# Dust1_carrier_6.net
KiCad netlist of a schematic drawn in Altium Designer
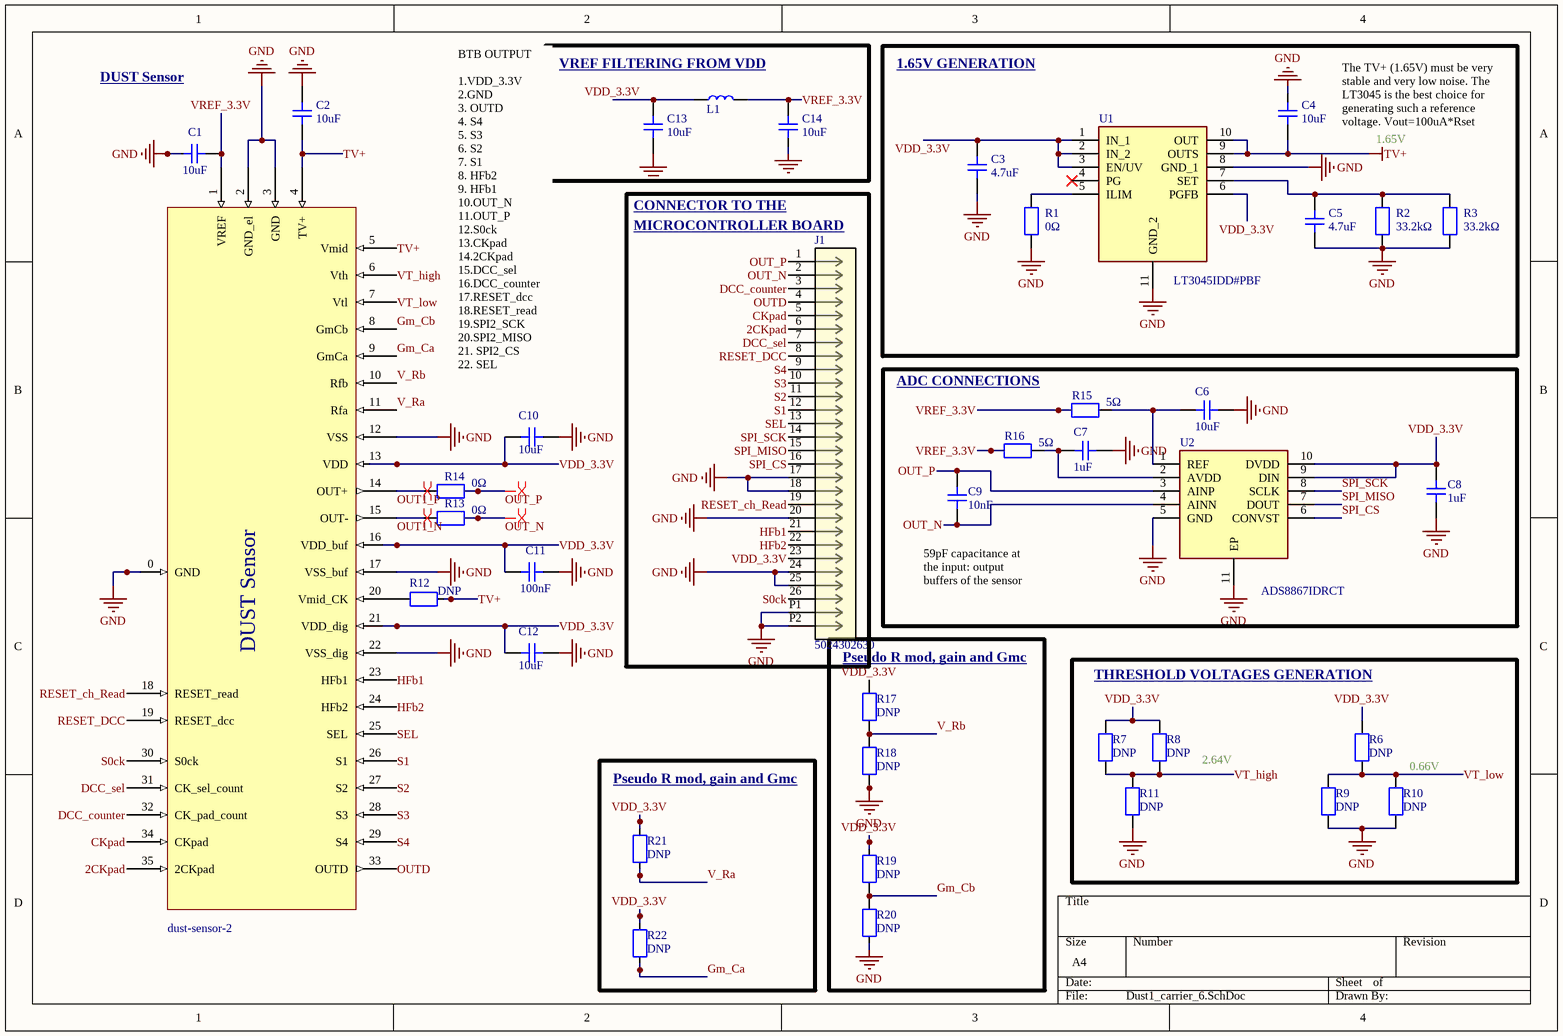
[diagram p0: Dust1_carrier_6.SchDoc]

(export (version "E")
  (design (tool "Eeschema 10.0.6"))
  (components
    (comp (ref "C1")
      (value "10uF")
      (footprint "CAP_0402")
      (libsource (lib "I3N - LABSAMP") (part "CAP_0402"))
    )
    (comp (ref "C2")
      (value "10uF")
      (footprint "CAP_0402")
      (libsource (lib "I3N - LABSAMP") (part "CAP_0402"))
    )
    (comp (ref "C3")
      (value "4.7uF")
      (footprint "CAP_0402")
      (libsource (lib "I3N - LABSAMP") (part "CAP_0402"))
    )
    (comp (ref "C4")
      (value "10uF")
      (footprint "CAP_0402")
      (libsource (lib "I3N - LABSAMP") (part "CAP_0402"))
    )
    (comp (ref "C5")
      (value "4.7uF")
      (footprint "CAP_0402")
      (libsource (lib "I3N - LABSAMP") (part "CAP_0402"))
    )
    (comp (ref "C6")
      (value "10uF")
      (footprint "CAP_0402")
      (libsource (lib "I3N - LABSAMP") (part "CAP_0402"))
    )
    (comp (ref "C7") (value "1uF") (footprint "CAP_0402") (libsource (lib "I3N - LABSAMP") (part "CAP_0402")))
    (comp (ref "C8") (value "1uF") (footprint "CAP_0402") (libsource (lib "I3N - LABSAMP") (part "CAP_0402")))
    (comp (ref "C9")
      (value "10nF")
      (footprint "CAP_0402")
      (libsource (lib "I3N - LABSAMP") (part "CAP_0402"))
    )
    (comp (ref "C10")
      (value "10uF")
      (footprint "CAP_0402")
      (libsource (lib "I3N - LABSAMP") (part "CAP_0402"))
    )
    (comp (ref "C11")
      (value "100nF")
      (footprint "CAP_0402")
      (libsource (lib "I3N - LABSAMP") (part "CAP_0402"))
    )
    (comp (ref "C12")
      (value "10uF")
      (footprint "CAP_0402")
      (libsource (lib "I3N - LABSAMP") (part "CAP_0402"))
    )
    (comp (ref "C13")
      (value "10uF")
      (footprint "CAP_0402")
      (libsource (lib "I3N - LABSAMP") (part "CAP_0402"))
    )
    (comp (ref "C14")
      (value "10uF")
      (footprint "CAP_0402")
      (libsource (lib "I3N - LABSAMP") (part "CAP_0402"))
    )
    (comp (ref "dust-sensor-2")
      (value "dust-sensor-2")
      (footprint "dust-sensor-2-Footprint-1")
      (description "dust-sensor-v2-2025")
      (libsource (lib "I3N - LABSAMP") (part "GND"))
    )
    (comp (ref "J1")
      (value "5024302630")
      (footprint "CON_5024302630_MOL")
      (fields (field (name "COPYRIGHT") "Copyright (C) 2025 Ultra Librarian. All rights reserved."))
      (libsource (lib "I3N - LABSAMP") (part "5024302630"))
    )
    (comp (ref "L1")
      (value "IND_0603")
      (footprint "IND_0603")
      (description "Generic 0603 Inductor")
      (libsource (lib "I3N - LABSAMP") (part "IND_0603"))
    )
    (comp (ref "R1")
      (value "0Ω")
      (footprint "RES_0402")
      (description "Resistor SMD 0402 Generic")
      (libsource (lib "I3N - LABSAMP") (part "RES_0402"))
    )
    (comp (ref "R2")
      (value "33.2kΩ")
      (footprint "RES_0402")
      (description "Resistor SMD 0402 Generic")
      (libsource (lib "I3N - LABSAMP") (part "RES_0402"))
    )
    (comp (ref "R3")
      (value "33.2kΩ")
      (footprint "RES_0402")
      (description "Resistor SMD 0402 Generic")
      (libsource (lib "I3N - LABSAMP") (part "RES_0402"))
    )
    (comp (ref "R6")
      (value "DNP")
      (footprint "RES_0402")
      (description "Resistor SMD 0402 Generic")
      (libsource (lib "I3N - LABSAMP") (part "RES_0402"))
    )
    (comp (ref "R7")
      (value "DNP")
      (footprint "RES_0402")
      (description "Resistor SMD 0402 Generic")
      (libsource (lib "I3N - LABSAMP") (part "RES_0402"))
    )
    (comp (ref "R8")
      (value "DNP")
      (footprint "RES_0402")
      (description "Resistor SMD 0402 Generic")
      (libsource (lib "I3N - LABSAMP") (part "RES_0402"))
    )
    (comp (ref "R9")
      (value "DNP")
      (footprint "RES_0402")
      (description "Resistor SMD 0402 Generic")
      (libsource (lib "I3N - LABSAMP") (part "RES_0402"))
    )
    (comp (ref "R10")
      (value "DNP")
      (footprint "RES_0402")
      (description "Resistor SMD 0402 Generic")
      (libsource (lib "I3N - LABSAMP") (part "RES_0402"))
    )
    (comp (ref "R11")
      (value "DNP")
      (footprint "RES_0402")
      (description "Resistor SMD 0402 Generic")
      (libsource (lib "I3N - LABSAMP") (part "RES_0402"))
    )
    (comp (ref "R12")
      (value "DNP")
      (footprint "RES_0402")
      (description "Resistor SMD 0402 Generic")
      (libsource (lib "I3N - LABSAMP") (part "RES_0402"))
    )
    (comp (ref "R13")
      (value "0Ω")
      (footprint "RES_0402")
      (description "Resistor SMD 0402 Generic")
      (libsource (lib "I3N - LABSAMP") (part "RES_0402"))
    )
    (comp (ref "R14")
      (value "0Ω")
      (footprint "RES_0402")
      (description "Resistor SMD 0402 Generic")
      (libsource (lib "I3N - LABSAMP") (part "RES_0402"))
    )
    (comp (ref "R15")
      (value "5Ω")
      (footprint "RES_0402")
      (description "Resistor SMD 0402 Generic")
      (libsource (lib "I3N - LABSAMP") (part "RES_0402"))
    )
    (comp (ref "R16")
      (value "5Ω")
      (footprint "RES_0402")
      (description "Resistor SMD 0402 Generic")
      (libsource (lib "I3N - LABSAMP") (part "RES_0402"))
    )
    (comp (ref "R17")
      (value "DNP")
      (footprint "RES_0402")
      (description "Resistor SMD 0402 Generic")
      (libsource (lib "I3N - LABSAMP") (part "RES_0402"))
    )
    (comp (ref "R18")
      (value "DNP")
      (footprint "RES_0402")
      (description "Resistor SMD 0402 Generic")
      (libsource (lib "I3N - LABSAMP") (part "RES_0402"))
    )
    (comp (ref "R19")
      (value "DNP")
      (footprint "RES_0402")
      (description "Resistor SMD 0402 Generic")
      (libsource (lib "I3N - LABSAMP") (part "RES_0402"))
    )
    (comp (ref "R20")
      (value "DNP")
      (footprint "RES_0402")
      (description "Resistor SMD 0402 Generic")
      (libsource (lib "I3N - LABSAMP") (part "RES_0402"))
    )
    (comp (ref "R21")
      (value "DNP")
      (footprint "RES_0402")
      (description "Resistor SMD 0402 Generic")
      (libsource (lib "I3N - LABSAMP") (part "RES_0402"))
    )
    (comp (ref "R22")
      (value "DNP")
      (footprint "RES_0402")
      (description "Resistor SMD 0402 Generic")
      (libsource (lib "I3N - LABSAMP") (part "RES_0402"))
    )
    (comp (ref "U1")
      (value "LT3045IDD#PBF")
      (footprint "SON50P300X300X80-11N-D")
      (description "Linear Technology LT3045IDD#PBF, LDO Regulator, 500mA Adjustable, 0  15 V, +/-1% 10-Pin, DFN")
      (fields (field (name "MOUSER PART NUMBER") "584-LT3045IDD#PBF"))
      (libsource (lib "I3N - LABSAMP") (part "LT3045IDD#PBF"))
    )
    (comp (ref "U2")
      (value "ADS8867IDRCT")
      (footprint "SON50P300X300X100-11N-D")
      (description "16-Bit, 100-kSPS, Serial Interface, microPower, Miniature, Truly-Differential Input, SAR ADC")
      (fields (field (name "MOUSER PART NUMBER") "595-ADS8867IDRCT"))
      (libsource (lib "I3N - LABSAMP") (part "ADS8867IDRCT"))
    )
  )
  (nets
    (net (code "1") (name "/2CKpad") (class "Default")
      (node (ref "J1") (pin "6") (pinfunction "6_6") (pintype "passive"))
      (node (ref "dust-sensor-2") (pin "35") (pinfunction "2CKpad_35") (pintype "input"))
    )
    (net (code "2") (name "/CKpad") (class "Default")
      (node (ref "J1") (pin "5") (pinfunction "5_5") (pintype "passive"))
      (node (ref "dust-sensor-2") (pin "34") (pinfunction "CKpad_34") (pintype "input"))
    )
    (net (code "3") (name "/DCC_counter") (class "Default")
      (node (ref "J1") (pin "3") (pinfunction "3_3") (pintype "passive"))
      (node (ref "dust-sensor-2") (pin "32") (pinfunction "CK_pad_count_32") (pintype "input"))
    )
    (net (code "4") (name "/DCC_sel") (class "Default")
      (node (ref "J1") (pin "7") (pinfunction "7_7") (pintype "passive"))
      (node (ref "dust-sensor-2") (pin "31") (pinfunction "CK_sel_count_31") (pintype "input"))
    )
    (net (code "5") (name "/Gm_Ca") (class "Default")
      (node (ref "R22") (pin "1") (pintype "passive"))
      (node (ref "dust-sensor-2") (pin "9") (pinfunction "GmCa_9") (pintype "input"))
    )
    (net (code "6") (name "/Gm_Cb") (class "Default")
      (node (ref "R19") (pin "1") (pintype "passive"))
      (node (ref "R20") (pin "2") (pintype "passive"))
      (node (ref "dust-sensor-2") (pin "8") (pinfunction "GmCb_8") (pintype "input"))
    )
    (net (code "7") (name "/HFb1") (class "Default")
      (node (ref "J1") (pin "21") (pinfunction "21_21") (pintype "passive"))
      (node (ref "dust-sensor-2") (pin "23") (pinfunction "HFb1_23") (pintype "input"))
    )
    (net (code "8") (name "/HFb2") (class "Default")
      (node (ref "J1") (pin "22") (pinfunction "22_22") (pintype "passive"))
      (node (ref "dust-sensor-2") (pin "24") (pinfunction "HFb2_24") (pintype "input"))
    )
    (net (code "9") (name "/OUT1_N") (class "Default")
      (node (ref "R13") (pin "2") (pintype "passive"))
      (node (ref "dust-sensor-2") (pin "15") (pinfunction "OUT-_15") (pintype "output"))
    )
    (net (code "10") (name "/OUT1_P") (class "Default")
      (node (ref "R14") (pin "2") (pintype "passive"))
      (node (ref "dust-sensor-2") (pin "14") (pinfunction "OUT+_14") (pintype "output"))
    )
    (net (code "11") (name "/OUTD") (class "Default")
      (node (ref "J1") (pin "4") (pinfunction "4_4") (pintype "passive"))
      (node (ref "dust-sensor-2") (pin "33") (pinfunction "OUTD_33") (pintype "output"))
    )
    (net (code "12") (name "/OUT_N") (class "Default")
      (node (ref "C9") (pin "2") (pintype "passive"))
      (node (ref "J1") (pin "2") (pinfunction "2_2") (pintype "passive"))
      (node (ref "R13") (pin "1") (pintype "passive"))
      (node (ref "U2") (pin "4") (pinfunction "AINN_4") (pintype "passive"))
    )
    (net (code "13") (name "/OUT_P") (class "Default")
      (node (ref "C9") (pin "1") (pintype "passive"))
      (node (ref "J1") (pin "1") (pinfunction "1_1") (pintype "passive"))
      (node (ref "R14") (pin "1") (pintype "passive"))
      (node (ref "U2") (pin "3") (pinfunction "AINP_3") (pintype "passive"))
    )
    (net (code "14") (name "/RESET_DCC") (class "Default")
      (node (ref "J1") (pin "8") (pinfunction "8_8") (pintype "passive"))
      (node (ref "dust-sensor-2") (pin "19") (pinfunction "RESET_dcc_19") (pintype "input"))
    )
    (net (code "15") (name "/RESET_ch_Read") (class "Default")
      (node (ref "J1") (pin "19") (pinfunction "19_19") (pintype "passive"))
      (node (ref "dust-sensor-2") (pin "18") (pinfunction "RESET_read_18") (pintype "input"))
    )
    (net (code "16") (name "/S0ck") (class "Default")
      (node (ref "J1") (pin "26") (pinfunction "26_26") (pintype "passive"))
      (node (ref "dust-sensor-2") (pin "30") (pinfunction "S0ck_30") (pintype "input"))
    )
    (net (code "17") (name "/S1") (class "Default")
      (node (ref "J1") (pin "12") (pinfunction "12_12") (pintype "passive"))
      (node (ref "dust-sensor-2") (pin "26") (pinfunction "S1_26") (pintype "input"))
    )
    (net (code "18") (name "/S2") (class "Default")
      (node (ref "J1") (pin "11") (pinfunction "11_11") (pintype "passive"))
      (node (ref "dust-sensor-2") (pin "27") (pinfunction "S2_27") (pintype "input"))
    )
    (net (code "19") (name "/S3") (class "Default")
      (node (ref "J1") (pin "10") (pinfunction "10_10") (pintype "passive"))
      (node (ref "dust-sensor-2") (pin "28") (pinfunction "S3_28") (pintype "input"))
    )
    (net (code "20") (name "/S4") (class "Default")
      (node (ref "J1") (pin "9") (pinfunction "9_9") (pintype "passive"))
      (node (ref "dust-sensor-2") (pin "29") (pinfunction "S4_29") (pintype "input"))
    )
    (net (code "21") (name "/SEL") (class "Default")
      (node (ref "J1") (pin "13") (pinfunction "13_13") (pintype "passive"))
      (node (ref "dust-sensor-2") (pin "25") (pinfunction "SEL_25") (pintype "input"))
    )
    (net (code "22") (name "/SPI_CS") (class "Default")
      (node (ref "J1") (pin "16") (pinfunction "16_16") (pintype "passive"))
      (node (ref "U2") (pin "6") (pinfunction "CONVST_6") (pintype "passive"))
    )
    (net (code "23") (name "/SPI_MISO") (class "Default")
      (node (ref "J1") (pin "15") (pinfunction "15_15") (pintype "passive"))
      (node (ref "U2") (pin "7") (pinfunction "DOUT_7") (pintype "passive"))
    )
    (net (code "24") (name "/SPI_SCK") (class "Default")
      (node (ref "J1") (pin "14") (pinfunction "14_14") (pintype "passive"))
      (node (ref "U2") (pin "8") (pinfunction "SCLK_8") (pintype "passive"))
    )
    (net (code "25") (name "/VDD_3.3V") (class "Default")
      (node (ref "C10") (pin "2") (pintype "passive"))
      (node (ref "C11") (pin "2") (pintype "passive"))
      (node (ref "C12") (pin "2") (pintype "passive"))
      (node (ref "C13") (pin "2") (pintype "passive"))
      (node (ref "C3") (pin "2") (pintype "passive"))
      (node (ref "C8") (pin "1") (pintype "passive"))
      (node (ref "J1") (pin "23") (pinfunction "23_23") (pintype "passive"))
      (node (ref "L1") (pin "1") (pintype "passive"))
      (node (ref "R17") (pin "2") (pintype "passive"))
      (node (ref "R19") (pin "2") (pintype "passive"))
      (node (ref "R21") (pin "2") (pintype "passive"))
      (node (ref "R22") (pin "2") (pintype "passive"))
      (node (ref "R6") (pin "2") (pintype "passive"))
      (node (ref "R7") (pin "2") (pintype "passive"))
      (node (ref "R8") (pin "2") (pintype "passive"))
      (node (ref "U1") (pin "1") (pinfunction "IN_1_1") (pintype "passive"))
      (node (ref "U1") (pin "2") (pinfunction "IN_2_2") (pintype "passive"))
      (node (ref "U1") (pin "3") (pinfunction "EN/UV_3") (pintype "passive"))
      (node (ref "U1") (pin "6") (pinfunction "PGFB_6") (pintype "passive"))
      (node (ref "U2") (pin "10") (pinfunction "DVDD_10") (pintype "passive"))
      (node (ref "U2") (pin "9") (pinfunction "DIN_9") (pintype "passive"))
      (node (ref "dust-sensor-2") (pin "13") (pinfunction "VDD_13") (pintype "input"))
      (node (ref "dust-sensor-2") (pin "16") (pinfunction "VDD_buf_16") (pintype "input"))
      (node (ref "dust-sensor-2") (pin "21") (pinfunction "VDD_dig_21") (pintype "input"))
    )
    (net (code "26") (name "/VREF_3.3V") (class "Default")
      (node (ref "C1") (pin "1") (pintype "passive"))
      (node (ref "C14") (pin "2") (pintype "passive"))
      (node (ref "L1") (pin "2") (pintype "passive"))
      (node (ref "R15") (pin "2") (pintype "passive"))
      (node (ref "R16") (pin "2") (pintype "passive"))
      (node (ref "dust-sensor-2") (pin "1") (pinfunction "VREF_1") (pintype "input"))
    )
    (net (code "27") (name "/VT_high") (class "Default")
      (node (ref "R11") (pin "2") (pintype "passive"))
      (node (ref "R7") (pin "1") (pintype "passive"))
      (node (ref "R8") (pin "1") (pintype "passive"))
      (node (ref "dust-sensor-2") (pin "6") (pinfunction "Vth_6") (pintype "input"))
    )
    (net (code "28") (name "/VT_low") (class "Default")
      (node (ref "R10") (pin "2") (pintype "passive"))
      (node (ref "R6") (pin "1") (pintype "passive"))
      (node (ref "R9") (pin "2") (pintype "passive"))
      (node (ref "dust-sensor-2") (pin "7") (pinfunction "Vtl_7") (pintype "input"))
    )
    (net (code "29") (name "/V_Ra") (class "Default")
      (node (ref "R21") (pin "1") (pintype "passive"))
      (node (ref "dust-sensor-2") (pin "11") (pinfunction "Rfa_11") (pintype "input"))
    )
    (net (code "30") (name "/V_Rb") (class "Default")
      (node (ref "R17") (pin "1") (pintype "passive"))
      (node (ref "R18") (pin "2") (pintype "passive"))
      (node (ref "dust-sensor-2") (pin "10") (pinfunction "Rfb_10") (pintype "input"))
    )
    (net (code "31") (name "GND") (class "Default")
      (node (ref "C1") (pin "2") (pintype "passive"))
      (node (ref "C10") (pin "1") (pintype "passive"))
      (node (ref "C11") (pin "1") (pintype "passive"))
      (node (ref "C12") (pin "1") (pintype "passive"))
      (node (ref "C13") (pin "1") (pintype "passive"))
      (node (ref "C14") (pin "1") (pintype "passive"))
      (node (ref "C2") (pin "2") (pintype "passive"))
      (node (ref "C3") (pin "1") (pintype "passive"))
      (node (ref "C4") (pin "2") (pintype "passive"))
      (node (ref "C5") (pin "1") (pintype "passive"))
      (node (ref "C6") (pin "1") (pintype "passive"))
      (node (ref "C7") (pin "1") (pintype "passive"))
      (node (ref "C8") (pin "2") (pintype "passive"))
      (node (ref "J1") (pin "17") (pinfunction "17_17") (pintype "passive"))
      (node (ref "J1") (pin "18") (pinfunction "18_18") (pintype "passive"))
      (node (ref "J1") (pin "20") (pinfunction "20_20") (pintype "passive"))
      (node (ref "J1") (pin "24") (pinfunction "24_24") (pintype "passive"))
      (node (ref "J1") (pin "25") (pinfunction "25_25") (pintype "passive"))
      (node (ref "J1") (pin "P1") (pinfunction "P1_P1") (pintype "passive"))
      (node (ref "J1") (pin "P2") (pinfunction "P2_P2") (pintype "passive"))
      (node (ref "R1") (pin "1") (pintype "passive"))
      (node (ref "R10") (pin "1") (pintype "passive"))
      (node (ref "R11") (pin "1") (pintype "passive"))
      (node (ref "R18") (pin "1") (pintype "passive"))
      (node (ref "R2") (pin "1") (pintype "passive"))
      (node (ref "R20") (pin "1") (pintype "passive"))
      (node (ref "R3") (pin "1") (pintype "passive"))
      (node (ref "R9") (pin "1") (pintype "passive"))
      (node (ref "U1") (pin "11") (pinfunction "GND_2_11") (pintype "passive"))
      (node (ref "U1") (pin "8") (pinfunction "GND_1_8") (pintype "passive"))
      (node (ref "U2") (pin "11") (pinfunction "EP_11") (pintype "passive"))
      (node (ref "U2") (pin "5") (pinfunction "GND_5") (pintype "passive"))
      (node (ref "dust-sensor-2") (pin "0") (pinfunction "GND_0") (pintype "input"))
      (node (ref "dust-sensor-2") (pin "12") (pinfunction "VSS_12") (pintype "input"))
      (node (ref "dust-sensor-2") (pin "17") (pinfunction "VSS_buf_17") (pintype "input"))
      (node (ref "dust-sensor-2") (pin "2") (pinfunction "GND_el_2") (pintype "input"))
      (node (ref "dust-sensor-2") (pin "22") (pinfunction "VSS_dig_22") (pintype "input"))
      (node (ref "dust-sensor-2") (pin "3") (pinfunction "GND_3") (pintype "input"))
    )
    (net (code "32") (name "Net-(U1-ILIM)") (class "Default")
      (node (ref "R1") (pin "2") (pintype "passive"))
      (node (ref "U1") (pin "5") (pinfunction "ILIM_5") (pintype "passive"))
    )
    (net (code "33") (name "Net-(U1-SET)") (class "Default")
      (node (ref "C5") (pin "2") (pintype "passive"))
      (node (ref "R2") (pin "2") (pintype "passive"))
      (node (ref "R3") (pin "2") (pintype "passive"))
      (node (ref "U1") (pin "7") (pinfunction "SET_7") (pintype "passive"))
    )
    (net (code "34") (name "Net-(U2-AVDD)") (class "Default")
      (node (ref "C7") (pin "2") (pintype "passive"))
      (node (ref "R16") (pin "1") (pintype "passive"))
      (node (ref "U2") (pin "2") (pinfunction "AVDD_2") (pintype "passive"))
    )
    (net (code "35") (name "Net-(U2-REF)") (class "Default")
      (node (ref "C6") (pin "2") (pintype "passive"))
      (node (ref "R15") (pin "1") (pintype "passive"))
      (node (ref "U2") (pin "1") (pinfunction "REF_1") (pintype "passive"))
    )
    (net (code "36") (name "Net-(dust-sensor-2-Vmid_CK)") (class "Default")
      (node (ref "R12") (pin "2") (pintype "passive"))
      (node (ref "dust-sensor-2") (pin "20") (pinfunction "Vmid_CK_20") (pintype "input"))
    )
    (net (code "37") (name "TV+") (class "Default")
      (node (ref "C2") (pin "1") (pintype "passive"))
      (node (ref "C4") (pin "1") (pintype "passive"))
      (node (ref "R12") (pin "1") (pintype "passive"))
      (node (ref "U1") (pin "10") (pinfunction "OUT_10") (pintype "passive"))
      (node (ref "U1") (pin "9") (pinfunction "OUTS_9") (pintype "passive"))
      (node (ref "dust-sensor-2") (pin "4") (pinfunction "TV+_4") (pintype "input"))
      (node (ref "dust-sensor-2") (pin "5") (pinfunction "Vmid_5") (pintype "input"))
    )
    (net (code "38") (name "unconnected-(U1-PG-Pad4)") (class "Default")
      (node (ref "U1") (pin "4") (pinfunction "PG_4") (pintype "passive+no_connect"))
    )
  )
)
